# pinky_2_3.net
KiCad netlist of a schematic drawn in EAGLE
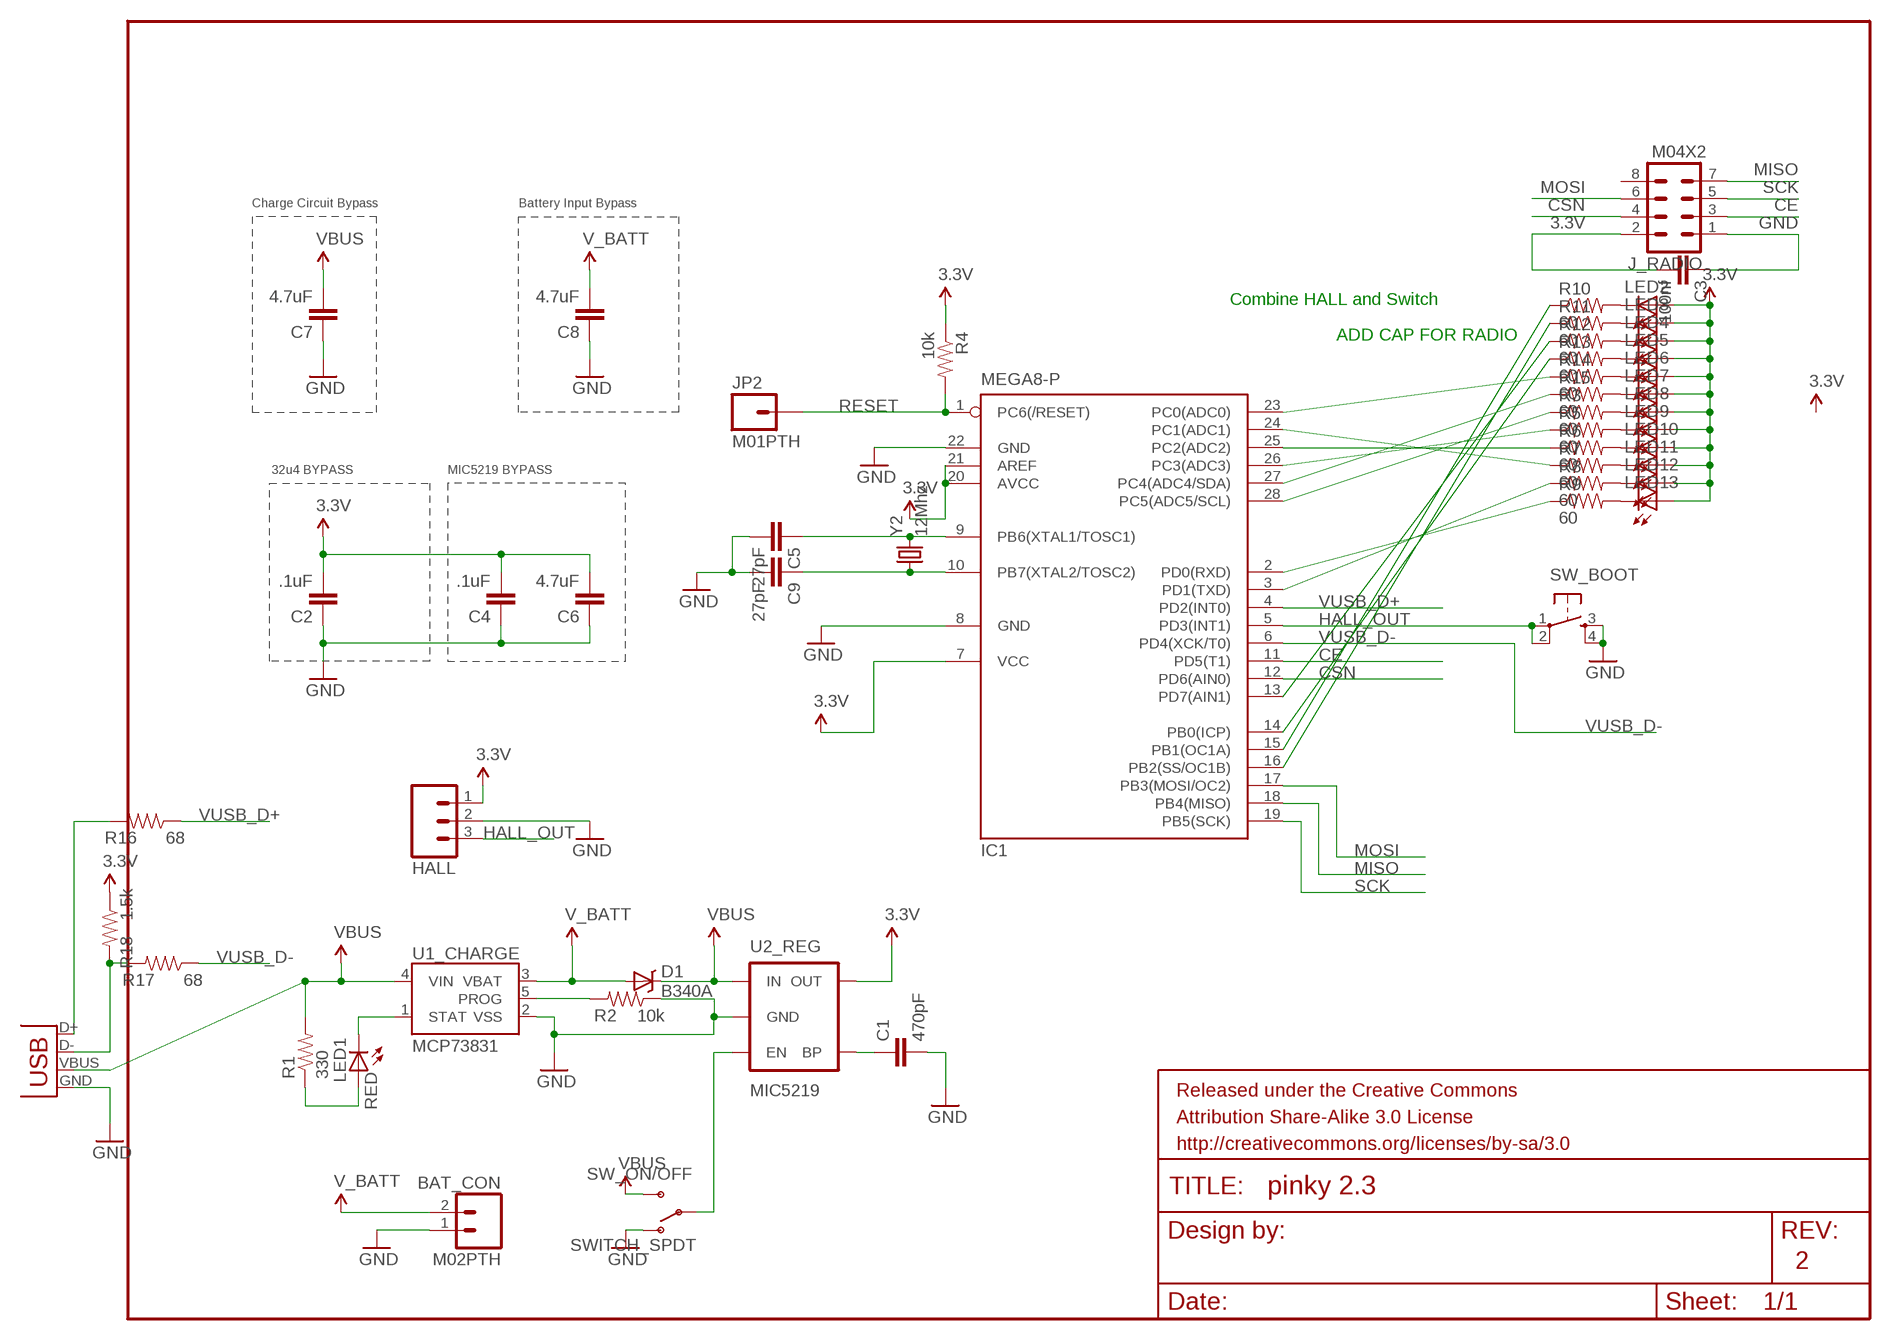
[diagram p0: schematic, sheet 1]

(export (version "E")
  (design (tool "Eeschema 10.0.6"))
  (components
    (comp (ref "BAT_CON")
      (value "M02PTH")
      (footprint "eagle-import:1X02")
      (libsource (lib "eagle-import") (part "M02PTH"))
    )
    (comp (ref "C1")
      (value "470pF")
      (footprint "eagle-import:1206")
      (libsource (lib "eagle-import") (part "CAP1206"))
    )
    (comp (ref "C2")
      (value ".1uF")
      (footprint "eagle-import:1206")
      (libsource (lib "eagle-import") (part "CAP1206"))
    )
    (comp (ref "C3")
      (value "100nf")
      (footprint "eagle-import:1206")
      (libsource (lib "eagle-import") (part "CAP1206"))
    )
    (comp (ref "C4")
      (value ".1uF")
      (footprint "eagle-import:1206")
      (libsource (lib "eagle-import") (part "CAP1206"))
    )
    (comp (ref "C5")
      (value "27pF")
      (footprint "eagle-import:1206")
      (libsource (lib "eagle-import") (part "CAP1206"))
    )
    (comp (ref "C6")
      (value "4.7uF")
      (footprint "eagle-import:1206")
      (libsource (lib "eagle-import") (part "CAP1206"))
    )
    (comp (ref "C7")
      (value "4.7uF")
      (footprint "eagle-import:1206")
      (libsource (lib "eagle-import") (part "CAP1206"))
    )
    (comp (ref "C8")
      (value "4.7uF")
      (footprint "eagle-import:1206")
      (libsource (lib "eagle-import") (part "CAP1206"))
    )
    (comp (ref "C9")
      (value "27pF")
      (footprint "eagle-import:1206")
      (libsource (lib "eagle-import") (part "CAP1206"))
    )
    (comp (ref "D1")
      (value "B340A")
      (footprint "eagle-import:SMA-DIODE")
      (libsource (lib "eagle-import") (part "DIODE-SCHOTTKY_"))
    )
    (comp (ref "HALL")
      (value "M03PTH")
      (footprint "eagle-import:1X03")
      (libsource (lib "eagle-import") (part "M03PTH"))
    )
    (comp (ref "IC1")
      (value "MEGA8-P")
      (footprint "eagle-import:DIL28-3")
      (libsource (lib "eagle-import") (part "MEGA8-P"))
    )
    (comp (ref "JP1")
      (value "USB-MB-H")
      (footprint "eagle-import:USB-MB-H")
      (libsource (lib "eagle-import") (part "USB-MB-H"))
    )
    (comp (ref "JP2")
      (value "M01PTH")
      (footprint "eagle-import:1X01")
      (libsource (lib "eagle-import") (part "M01PTH"))
    )
    (comp (ref "J_RADIO")
      (value "M04X2")
      (footprint "eagle-import:2X4")
      (libsource (lib "eagle-import") (part "M04X2"))
    )
    (comp (ref "LED1")
      (value "RED")
      (footprint "eagle-import:LED-1206")
      (libsource (lib "eagle-import") (part "LED1206"))
    )
    (comp (ref "LED2")
      (value "LED1206")
      (footprint "eagle-import:LED-1206")
      (libsource (lib "eagle-import") (part "LED1206"))
    )
    (comp (ref "LED3")
      (value "LED1206")
      (footprint "eagle-import:LED-1206")
      (libsource (lib "eagle-import") (part "LED1206"))
    )
    (comp (ref "LED4")
      (value "LED1206")
      (footprint "eagle-import:LED-1206")
      (libsource (lib "eagle-import") (part "LED1206"))
    )
    (comp (ref "LED5")
      (value "LED1206")
      (footprint "eagle-import:LED-1206")
      (libsource (lib "eagle-import") (part "LED1206"))
    )
    (comp (ref "LED6")
      (value "LED1206")
      (footprint "eagle-import:LED-1206")
      (libsource (lib "eagle-import") (part "LED1206"))
    )
    (comp (ref "LED7")
      (value "LED1206")
      (footprint "eagle-import:LED-1206")
      (libsource (lib "eagle-import") (part "LED1206"))
    )
    (comp (ref "LED8")
      (value "LED1206")
      (footprint "eagle-import:LED-1206")
      (libsource (lib "eagle-import") (part "LED1206"))
    )
    (comp (ref "LED9")
      (value "LED1206")
      (footprint "eagle-import:LED-1206")
      (libsource (lib "eagle-import") (part "LED1206"))
    )
    (comp (ref "LED10")
      (value "LED1206")
      (footprint "eagle-import:LED-1206")
      (libsource (lib "eagle-import") (part "LED1206"))
    )
    (comp (ref "LED11")
      (value "LED1206")
      (footprint "eagle-import:LED-1206")
      (libsource (lib "eagle-import") (part "LED1206"))
    )
    (comp (ref "LED12")
      (value "LED1206")
      (footprint "eagle-import:LED-1206")
      (libsource (lib "eagle-import") (part "LED1206"))
    )
    (comp (ref "LED13")
      (value "LED1206")
      (footprint "eagle-import:LED-1206")
      (libsource (lib "eagle-import") (part "LED1206"))
    )
    (comp (ref "R1")
      (value "330")
      (footprint "eagle-import:1206")
      (libsource (lib "eagle-import") (part "RESISTOR1206"))
    )
    (comp (ref "R2")
      (value "10k")
      (footprint "eagle-import:1206")
      (libsource (lib "eagle-import") (part "RESISTOR1206"))
    )
    (comp (ref "R3")
      (value "60")
      (footprint "eagle-import:1206")
      (libsource (lib "eagle-import") (part "RESISTOR1206"))
    )
    (comp (ref "R4")
      (value "10k")
      (footprint "eagle-import:1206")
      (libsource (lib "eagle-import") (part "RESISTOR1206"))
    )
    (comp (ref "R5")
      (value "60")
      (footprint "eagle-import:1206")
      (libsource (lib "eagle-import") (part "RESISTOR1206"))
    )
    (comp (ref "R6")
      (value "60")
      (footprint "eagle-import:1206")
      (libsource (lib "eagle-import") (part "RESISTOR1206"))
    )
    (comp (ref "R7")
      (value "60")
      (footprint "eagle-import:1206")
      (libsource (lib "eagle-import") (part "RESISTOR1206"))
    )
    (comp (ref "R8")
      (value "60")
      (footprint "eagle-import:1206")
      (libsource (lib "eagle-import") (part "RESISTOR1206"))
    )
    (comp (ref "R9")
      (value "60")
      (footprint "eagle-import:1206")
      (libsource (lib "eagle-import") (part "RESISTOR1206"))
    )
    (comp (ref "R10")
      (value "60")
      (footprint "eagle-import:1206")
      (libsource (lib "eagle-import") (part "RESISTOR1206"))
    )
    (comp (ref "R11")
      (value "60")
      (footprint "eagle-import:1206")
      (libsource (lib "eagle-import") (part "RESISTOR1206"))
    )
    (comp (ref "R12")
      (value "60")
      (footprint "eagle-import:1206")
      (libsource (lib "eagle-import") (part "RESISTOR1206"))
    )
    (comp (ref "R13")
      (value "60")
      (footprint "eagle-import:1206")
      (libsource (lib "eagle-import") (part "RESISTOR1206"))
    )
    (comp (ref "R14")
      (value "60")
      (footprint "eagle-import:1206")
      (libsource (lib "eagle-import") (part "RESISTOR1206"))
    )
    (comp (ref "R15")
      (value "60")
      (footprint "eagle-import:1206")
      (libsource (lib "eagle-import") (part "RESISTOR1206"))
    )
    (comp (ref "R16")
      (value "68")
      (footprint "eagle-import:1206")
      (libsource (lib "eagle-import") (part "RESISTOR1206"))
    )
    (comp (ref "R17")
      (value "68")
      (footprint "eagle-import:1206")
      (libsource (lib "eagle-import") (part "RESISTOR1206"))
    )
    (comp (ref "R18")
      (value "1.5k")
      (footprint "eagle-import:1206")
      (libsource (lib "eagle-import") (part "RESISTOR1206"))
    )
    (comp (ref "SW_BOOT")
      (value "TAC_SWITCHPTH")
      (footprint "eagle-import:TACTILE-PTH")
      (libsource (lib "eagle-import") (part "TAC_SWITCHPTH"))
    )
    (comp (ref "SW_ON/OFF")
      (value "SWITCH_SPDT")
      (footprint "eagle-import:KPS-1290")
      (libsource (lib "eagle-import") (part "SWITCH_SPDT"))
    )
    (comp (ref "U1_CHARGE")
      (value "MCP73831")
      (footprint "eagle-import:SOT23-5")
      (libsource (lib "eagle-import") (part "MCP73831"))
    )
    (comp (ref "U2_REG")
      (value "MIC5219")
      (footprint "eagle-import:SOT23-5")
      (libsource (lib "eagle-import") (part "V_REG_MIC5219SMD"))
    )
    (comp (ref "Y2")
      (value "12Mhz")
      (footprint "eagle-import:HC49US")
      (libsource (lib "eagle-import") (part "CRYSTALHC49US"))
    )
  )
  (nets
    (net (code "1") (name "/CE") (class "Default")
      (node (ref "IC1") (pin "11") (pinfunction "PD5(T1)_11") (pintype "bidirectional"))
      (node (ref "J_RADIO") (pin "3") (pinfunction "3_3") (pintype "passive"))
    )
    (net (code "2") (name "/CSN") (class "Default")
      (node (ref "IC1") (pin "12") (pinfunction "PD6(AIN0)_12") (pintype "bidirectional"))
      (node (ref "J_RADIO") (pin "4") (pinfunction "4_4") (pintype "passive"))
    )
    (net (code "3") (name "/HALL_OUT") (class "Default")
      (node (ref "HALL") (pin "3") (pinfunction "3_3") (pintype "passive"))
      (node (ref "IC1") (pin "5") (pinfunction "PD3(INT1)_5") (pintype "bidirectional"))
      (node (ref "SW_BOOT") (pin "1") (pinfunction "1_1") (pintype "passive"))
      (node (ref "SW_BOOT") (pin "2") (pinfunction "2_2") (pintype "passive"))
    )
    (net (code "4") (name "/MISO") (class "Default")
      (node (ref "IC1") (pin "18") (pinfunction "PB4(MISO)_18") (pintype "bidirectional"))
      (node (ref "J_RADIO") (pin "7") (pinfunction "7_7") (pintype "passive"))
    )
    (net (code "5") (name "/MOSI") (class "Default")
      (node (ref "IC1") (pin "17") (pinfunction "PB3(MOSI/OC2)_17") (pintype "bidirectional"))
      (node (ref "J_RADIO") (pin "6") (pinfunction "6_6") (pintype "passive"))
    )
    (net (code "6") (name "/RESET") (class "Default")
      (node (ref "IC1") (pin "1") (pinfunction "PC6(/RESET)_1") (pintype "bidirectional"))
      (node (ref "JP2") (pin "1") (pinfunction "1_1") (pintype "passive"))
      (node (ref "R4") (pin "2") (pinfunction "2_2") (pintype "passive"))
    )
    (net (code "7") (name "/SCK") (class "Default")
      (node (ref "IC1") (pin "19") (pinfunction "PB5(SCK)_19") (pintype "bidirectional"))
      (node (ref "J_RADIO") (pin "5") (pinfunction "5_5") (pintype "passive"))
    )
    (net (code "8") (name "/VUSB_D+") (class "Default")
      (node (ref "IC1") (pin "4") (pinfunction "PD2(INT0)_4") (pintype "bidirectional"))
      (node (ref "R16") (pin "1") (pinfunction "1_1") (pintype "passive"))
    )
    (net (code "9") (name "/VUSB_D-") (class "Default")
      (node (ref "IC1") (pin "6") (pinfunction "PD4(XCK/T0)_6") (pintype "bidirectional"))
      (node (ref "R17") (pin "1") (pinfunction "1_1") (pintype "passive"))
    )
    (net (code "10") (name "3.3V") (class "Default")
      (node (ref "C2") (pin "2") (pinfunction "2_2") (pintype "passive"))
      (node (ref "C3") (pin "2") (pinfunction "2_2") (pintype "passive"))
      (node (ref "C4") (pin "2") (pinfunction "2_2") (pintype "passive"))
      (node (ref "C6") (pin "2") (pinfunction "2_2") (pintype "passive"))
      (node (ref "HALL") (pin "1") (pinfunction "1_1") (pintype "passive"))
      (node (ref "IC1") (pin "20") (pinfunction "AVCC_20") (pintype "power_in"))
      (node (ref "IC1") (pin "21") (pinfunction "AREF_21") (pintype "passive"))
      (node (ref "IC1") (pin "7") (pinfunction "VCC_7") (pintype "power_in"))
      (node (ref "J_RADIO") (pin "2") (pinfunction "2_2") (pintype "passive"))
      (node (ref "LED10") (pin "A") (pinfunction "A_A") (pintype "passive"))
      (node (ref "LED11") (pin "A") (pinfunction "A_A") (pintype "passive"))
      (node (ref "LED12") (pin "A") (pinfunction "A_A") (pintype "passive"))
      (node (ref "LED13") (pin "A") (pinfunction "A_A") (pintype "passive"))
      (node (ref "LED2") (pin "A") (pinfunction "A_A") (pintype "passive"))
      (node (ref "LED3") (pin "A") (pinfunction "A_A") (pintype "passive"))
      (node (ref "LED4") (pin "A") (pinfunction "A_A") (pintype "passive"))
      (node (ref "LED5") (pin "A") (pinfunction "A_A") (pintype "passive"))
      (node (ref "LED6") (pin "A") (pinfunction "A_A") (pintype "passive"))
      (node (ref "LED7") (pin "A") (pinfunction "A_A") (pintype "passive"))
      (node (ref "LED8") (pin "A") (pinfunction "A_A") (pintype "passive"))
      (node (ref "LED9") (pin "A") (pinfunction "A_A") (pintype "passive"))
      (node (ref "R18") (pin "1") (pinfunction "1_1") (pintype "passive"))
      (node (ref "R4") (pin "1") (pinfunction "1_1") (pintype "passive"))
      (node (ref "U2_REG") (pin "5") (pinfunction "OUT_5") (pintype "passive"))
    )
    (net (code "11") (name "GND") (class "Default")
      (node (ref "BAT_CON") (pin "1") (pinfunction "1_1") (pintype "passive"))
      (node (ref "C1") (pin "2") (pinfunction "2_2") (pintype "passive"))
      (node (ref "C2") (pin "1") (pinfunction "1_1") (pintype "passive"))
      (node (ref "C3") (pin "1") (pinfunction "1_1") (pintype "passive"))
      (node (ref "C4") (pin "1") (pinfunction "1_1") (pintype "passive"))
      (node (ref "C5") (pin "2") (pinfunction "2_2") (pintype "passive"))
      (node (ref "C6") (pin "1") (pinfunction "1_1") (pintype "passive"))
      (node (ref "C7") (pin "1") (pinfunction "1_1") (pintype "passive"))
      (node (ref "C8") (pin "1") (pinfunction "1_1") (pintype "passive"))
      (node (ref "C9") (pin "2") (pinfunction "2_2") (pintype "passive"))
      (node (ref "HALL") (pin "2") (pinfunction "2_2") (pintype "passive"))
      (node (ref "IC1") (pin "22") (pinfunction "GND_22") (pintype "power_in"))
      (node (ref "IC1") (pin "8") (pinfunction "GND_8") (pintype "power_in"))
      (node (ref "JP1") (pin "GND") (pinfunction "GND_GND") (pintype "bidirectional"))
      (node (ref "J_RADIO") (pin "1") (pinfunction "1_1") (pintype "passive"))
      (node (ref "R2") (pin "1") (pinfunction "1_1") (pintype "passive"))
      (node (ref "SW_BOOT") (pin "3") (pinfunction "3_3") (pintype "passive"))
      (node (ref "SW_BOOT") (pin "4") (pinfunction "4_4") (pintype "passive"))
      (node (ref "SW_ON/OFF") (pin "O") (pinfunction "O_O") (pintype "passive"))
      (node (ref "U1_CHARGE") (pin "2") (pinfunction "VSS_2") (pintype "power_in"))
      (node (ref "U2_REG") (pin "2") (pinfunction "GND_2") (pintype "input"))
    )
    (net (code "12") (name "Net-(IC1-PB0(ICP))") (class "Default")
      (node (ref "IC1") (pin "14") (pinfunction "PB0(ICP)_14") (pintype "bidirectional"))
      (node (ref "R13") (pin "1") (pinfunction "1_1") (pintype "passive"))
    )
    (net (code "13") (name "Net-(IC1-PB1(OC1A))") (class "Default")
      (node (ref "IC1") (pin "15") (pinfunction "PB1(OC1A)_15") (pintype "bidirectional"))
      (node (ref "R10") (pin "1") (pinfunction "1_1") (pintype "passive"))
    )
    (net (code "14") (name "Net-(IC1-PB2(SS{slash}OC1B))") (class "Default")
      (node (ref "IC1") (pin "16") (pinfunction "PB2(SS/OC1B)_16") (pintype "bidirectional"))
      (node (ref "R11") (pin "1") (pinfunction "1_1") (pintype "passive"))
    )
    (net (code "15") (name "Net-(IC1-PB6(XTAL1{slash}TOSC1))") (class "Default")
      (node (ref "C5") (pin "1") (pinfunction "1_1") (pintype "passive"))
      (node (ref "IC1") (pin "9") (pinfunction "PB6(XTAL1/TOSC1)_9") (pintype "bidirectional"))
      (node (ref "Y2") (pin "2") (pinfunction "2_2") (pintype "passive"))
    )
    (net (code "16") (name "Net-(IC1-PB7(XTAL2{slash}TOSC2))") (class "Default")
      (node (ref "C9") (pin "1") (pinfunction "1_1") (pintype "passive"))
      (node (ref "IC1") (pin "10") (pinfunction "PB7(XTAL2/TOSC2)_10") (pintype "bidirectional"))
      (node (ref "Y2") (pin "1") (pinfunction "1_1") (pintype "passive"))
    )
    (net (code "17") (name "Net-(IC1-PC0(ADC0))") (class "Default")
      (node (ref "IC1") (pin "23") (pinfunction "PC0(ADC0)_23") (pintype "bidirectional"))
      (node (ref "R14") (pin "1") (pinfunction "1_1") (pintype "passive"))
    )
    (net (code "18") (name "Net-(IC1-PC1(ADC1))") (class "Default")
      (node (ref "IC1") (pin "24") (pinfunction "PC1(ADC1)_24") (pintype "bidirectional"))
      (node (ref "R7") (pin "1") (pinfunction "1_1") (pintype "passive"))
    )
    (net (code "19") (name "Net-(IC1-PC2(ADC2))") (class "Default")
      (node (ref "IC1") (pin "25") (pinfunction "PC2(ADC2)_25") (pintype "bidirectional"))
      (node (ref "R6") (pin "1") (pinfunction "1_1") (pintype "passive"))
    )
    (net (code "20") (name "Net-(IC1-PC3(ADC3))") (class "Default")
      (node (ref "IC1") (pin "26") (pinfunction "PC3(ADC3)_26") (pintype "bidirectional"))
      (node (ref "R5") (pin "1") (pinfunction "1_1") (pintype "passive"))
    )
    (net (code "21") (name "Net-(IC1-PC4(ADC4{slash}SDA))") (class "Default")
      (node (ref "IC1") (pin "27") (pinfunction "PC4(ADC4/SDA)_27") (pintype "bidirectional"))
      (node (ref "R15") (pin "1") (pinfunction "1_1") (pintype "passive"))
    )
    (net (code "22") (name "Net-(IC1-PC5(ADC5{slash}SCL))") (class "Default")
      (node (ref "IC1") (pin "28") (pinfunction "PC5(ADC5/SCL)_28") (pintype "bidirectional"))
      (node (ref "R3") (pin "1") (pinfunction "1_1") (pintype "passive"))
    )
    (net (code "23") (name "Net-(IC1-PD0(RXD))") (class "Default")
      (node (ref "IC1") (pin "2") (pinfunction "PD0(RXD)_2") (pintype "bidirectional"))
      (node (ref "R9") (pin "1") (pinfunction "1_1") (pintype "passive"))
    )
    (net (code "24") (name "Net-(IC1-PD1(TXD))") (class "Default")
      (node (ref "IC1") (pin "3") (pinfunction "PD1(TXD)_3") (pintype "bidirectional"))
      (node (ref "R8") (pin "1") (pinfunction "1_1") (pintype "passive"))
    )
    (net (code "25") (name "Net-(IC1-PD7(AIN1))") (class "Default")
      (node (ref "IC1") (pin "13") (pinfunction "PD7(AIN1)_13") (pintype "bidirectional"))
      (node (ref "R12") (pin "1") (pinfunction "1_1") (pintype "passive"))
    )
    (net (code "26") (name "Net-(JP1-PadD+)") (class "Default")
      (node (ref "JP1") (pin "D+") (pinfunction "D+_D+") (pintype "bidirectional"))
      (node (ref "R16") (pin "2") (pinfunction "2_2") (pintype "passive"))
    )
    (net (code "27") (name "Net-(JP1-PadD-)") (class "Default")
      (node (ref "JP1") (pin "D-") (pinfunction "D-_D-") (pintype "bidirectional"))
      (node (ref "R17") (pin "2") (pinfunction "2_2") (pintype "passive"))
      (node (ref "R18") (pin "2") (pinfunction "2_2") (pintype "passive"))
    )
    (net (code "28") (name "Net-(LED1-PadA)") (class "Default")
      (node (ref "LED1") (pin "A") (pinfunction "A_A") (pintype "passive"))
      (node (ref "R1") (pin "1") (pinfunction "1_1") (pintype "passive"))
    )
    (net (code "29") (name "Net-(LED2-PadC)") (class "Default")
      (node (ref "LED2") (pin "C") (pinfunction "C_C") (pintype "passive"))
      (node (ref "R10") (pin "2") (pinfunction "2_2") (pintype "passive"))
    )
    (net (code "30") (name "Net-(LED3-PadC)") (class "Default")
      (node (ref "LED3") (pin "C") (pinfunction "C_C") (pintype "passive"))
      (node (ref "R11") (pin "2") (pinfunction "2_2") (pintype "passive"))
    )
    (net (code "31") (name "Net-(LED4-PadC)") (class "Default")
      (node (ref "LED4") (pin "C") (pinfunction "C_C") (pintype "passive"))
      (node (ref "R12") (pin "2") (pinfunction "2_2") (pintype "passive"))
    )
    (net (code "32") (name "Net-(LED5-PadC)") (class "Default")
      (node (ref "LED5") (pin "C") (pinfunction "C_C") (pintype "passive"))
      (node (ref "R13") (pin "2") (pinfunction "2_2") (pintype "passive"))
    )
    (net (code "33") (name "Net-(LED6-PadC)") (class "Default")
      (node (ref "LED6") (pin "C") (pinfunction "C_C") (pintype "passive"))
      (node (ref "R14") (pin "2") (pinfunction "2_2") (pintype "passive"))
    )
    (net (code "34") (name "Net-(LED7-PadC)") (class "Default")
      (node (ref "LED7") (pin "C") (pinfunction "C_C") (pintype "passive"))
      (node (ref "R15") (pin "2") (pinfunction "2_2") (pintype "passive"))
    )
    (net (code "35") (name "Net-(LED8-PadC)") (class "Default")
      (node (ref "LED8") (pin "C") (pinfunction "C_C") (pintype "passive"))
      (node (ref "R3") (pin "2") (pinfunction "2_2") (pintype "passive"))
    )
    (net (code "36") (name "Net-(LED9-PadC)") (class "Default")
      (node (ref "LED9") (pin "C") (pinfunction "C_C") (pintype "passive"))
      (node (ref "R5") (pin "2") (pinfunction "2_2") (pintype "passive"))
    )
    (net (code "37") (name "Net-(LED10-PadC)") (class "Default")
      (node (ref "LED10") (pin "C") (pinfunction "C_C") (pintype "passive"))
      (node (ref "R6") (pin "2") (pinfunction "2_2") (pintype "passive"))
    )
    (net (code "38") (name "Net-(LED11-PadC)") (class "Default")
      (node (ref "LED11") (pin "C") (pinfunction "C_C") (pintype "passive"))
      (node (ref "R7") (pin "2") (pinfunction "2_2") (pintype "passive"))
    )
    (net (code "39") (name "Net-(LED12-PadC)") (class "Default")
      (node (ref "LED12") (pin "C") (pinfunction "C_C") (pintype "passive"))
      (node (ref "R8") (pin "2") (pinfunction "2_2") (pintype "passive"))
    )
    (net (code "40") (name "Net-(LED13-PadC)") (class "Default")
      (node (ref "LED13") (pin "C") (pinfunction "C_C") (pintype "passive"))
      (node (ref "R9") (pin "2") (pinfunction "2_2") (pintype "passive"))
    )
    (net (code "41") (name "Net-(U1_CHARGE-PROG)") (class "Default")
      (node (ref "R2") (pin "2") (pinfunction "2_2") (pintype "passive"))
      (node (ref "U1_CHARGE") (pin "5") (pinfunction "PROG_5") (pintype "input"))
    )
    (net (code "42") (name "Net-(U1_CHARGE-STAT)") (class "Default")
      (node (ref "LED1") (pin "C") (pinfunction "C_C") (pintype "passive"))
      (node (ref "U1_CHARGE") (pin "1") (pinfunction "STAT_1") (pintype "output"))
    )
    (net (code "43") (name "Net-(U2_REG-BP)") (class "Default")
      (node (ref "C1") (pin "1") (pinfunction "1_1") (pintype "passive"))
      (node (ref "U2_REG") (pin "4") (pinfunction "BP_4") (pintype "input"))
    )
    (net (code "44") (name "Net-(U2_REG-EN)") (class "Default")
      (node (ref "SW_ON/OFF") (pin "P") (pinfunction "P_P") (pintype "passive"))
      (node (ref "U2_REG") (pin "3") (pinfunction "EN_3") (pintype "input"))
    )
    (net (code "45") (name "VBUS") (class "Default")
      (node (ref "C7") (pin "2") (pinfunction "2_2") (pintype "passive"))
      (node (ref "D1") (pin "C") (pinfunction "C_C") (pintype "passive"))
      (node (ref "JP1") (pin "VBUS") (pinfunction "VBUS_VBUS") (pintype "bidirectional"))
      (node (ref "R1") (pin "2") (pinfunction "2_2") (pintype "passive"))
      (node (ref "SW_ON/OFF") (pin "S") (pinfunction "S_S") (pintype "passive"))
      (node (ref "U1_CHARGE") (pin "4") (pinfunction "VIN_4") (pintype "power_in"))
      (node (ref "U2_REG") (pin "1") (pinfunction "IN_1") (pintype "input"))
    )
    (net (code "46") (name "V_BATT") (class "Default")
      (node (ref "BAT_CON") (pin "2") (pinfunction "2_2") (pintype "passive"))
      (node (ref "C8") (pin "2") (pinfunction "2_2") (pintype "passive"))
      (node (ref "D1") (pin "A") (pinfunction "A_A") (pintype "passive"))
      (node (ref "U1_CHARGE") (pin "3") (pinfunction "VBAT_3") (pintype "power_in"))
    )
    (net (code "47") (name "unconnected-(J_RADIO-Pad8)") (class "Default")
      (node (ref "J_RADIO") (pin "8") (pinfunction "8_8") (pintype "passive"))
    )
  )
)
